# main.net
KiCad netlist of a schematic drawn in EAGLE
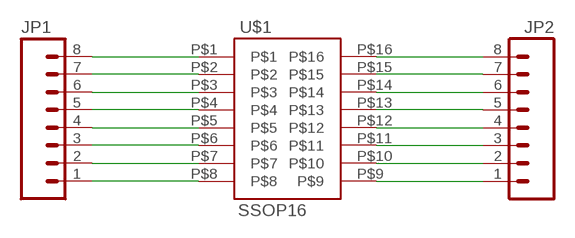
[diagram p0: schematic, sheet 1]

(export (version "E")
  (design (tool "Eeschema 10.0.6"))
  (components
    (comp (ref "JP1")
      (value "M08LONGPADS")
      (footprint "eagle-import:1X08_LONGPADS")
      (libsource (lib "eagle-import") (part "M08LONGPADS"))
    )
    (comp (ref "JP2")
      (value "M08LONGPADS")
      (footprint "eagle-import:1X08_LONGPADS")
      (libsource (lib "eagle-import") (part "M08LONGPADS"))
    )
    (comp (ref "U$1")
      (value "SSOP16")
      (footprint "eagle-import:SSOP16")
      (libsource (lib "eagle-import") (part "SSOP16"))
    )
  )
  (nets
    (net (code "1") (name "Net-(JP1-Pad1)") (class "Default")
      (node (ref "JP1") (pin "1") (pinfunction "1_1") (pintype "passive"))
      (node (ref "U$1") (pin "P$8") (pinfunction "P$8_P$8") (pintype "bidirectional"))
    )
    (net (code "2") (name "Net-(JP1-Pad2)") (class "Default")
      (node (ref "JP1") (pin "2") (pinfunction "2_2") (pintype "passive"))
      (node (ref "U$1") (pin "P$7") (pinfunction "P$7_P$7") (pintype "bidirectional"))
    )
    (net (code "3") (name "Net-(JP1-Pad3)") (class "Default")
      (node (ref "JP1") (pin "3") (pinfunction "3_3") (pintype "passive"))
      (node (ref "U$1") (pin "P$6") (pinfunction "P$6_P$6") (pintype "bidirectional"))
    )
    (net (code "4") (name "Net-(JP1-Pad4)") (class "Default")
      (node (ref "JP1") (pin "4") (pinfunction "4_4") (pintype "passive"))
      (node (ref "U$1") (pin "P$5") (pinfunction "P$5_P$5") (pintype "bidirectional"))
    )
    (net (code "5") (name "Net-(JP1-Pad5)") (class "Default")
      (node (ref "JP1") (pin "5") (pinfunction "5_5") (pintype "passive"))
      (node (ref "U$1") (pin "P$4") (pinfunction "P$4_P$4") (pintype "bidirectional"))
    )
    (net (code "6") (name "Net-(JP1-Pad6)") (class "Default")
      (node (ref "JP1") (pin "6") (pinfunction "6_6") (pintype "passive"))
      (node (ref "U$1") (pin "P$3") (pinfunction "P$3_P$3") (pintype "bidirectional"))
    )
    (net (code "7") (name "Net-(JP1-Pad7)") (class "Default")
      (node (ref "JP1") (pin "7") (pinfunction "7_7") (pintype "passive"))
      (node (ref "U$1") (pin "P$2") (pinfunction "P$2_P$2") (pintype "bidirectional"))
    )
    (net (code "8") (name "Net-(JP1-Pad8)") (class "Default")
      (node (ref "JP1") (pin "8") (pinfunction "8_8") (pintype "passive"))
      (node (ref "U$1") (pin "P$1") (pinfunction "P$1_P$1") (pintype "bidirectional"))
    )
    (net (code "9") (name "Net-(JP2-Pad1)") (class "Default")
      (node (ref "JP2") (pin "1") (pinfunction "1_1") (pintype "passive"))
      (node (ref "U$1") (pin "P$9") (pinfunction "P$9_P$9") (pintype "bidirectional"))
    )
    (net (code "10") (name "Net-(JP2-Pad2)") (class "Default")
      (node (ref "JP2") (pin "2") (pinfunction "2_2") (pintype "passive"))
      (node (ref "U$1") (pin "P$10") (pinfunction "P$10_P$10") (pintype "bidirectional"))
    )
    (net (code "11") (name "Net-(JP2-Pad3)") (class "Default")
      (node (ref "JP2") (pin "3") (pinfunction "3_3") (pintype "passive"))
      (node (ref "U$1") (pin "P$11") (pinfunction "P$11_P$11") (pintype "bidirectional"))
    )
    (net (code "12") (name "Net-(JP2-Pad4)") (class "Default")
      (node (ref "JP2") (pin "4") (pinfunction "4_4") (pintype "passive"))
      (node (ref "U$1") (pin "P$12") (pinfunction "P$12_P$12") (pintype "bidirectional"))
    )
    (net (code "13") (name "Net-(JP2-Pad5)") (class "Default")
      (node (ref "JP2") (pin "5") (pinfunction "5_5") (pintype "passive"))
      (node (ref "U$1") (pin "P$13") (pinfunction "P$13_P$13") (pintype "bidirectional"))
    )
    (net (code "14") (name "Net-(JP2-Pad6)") (class "Default")
      (node (ref "JP2") (pin "6") (pinfunction "6_6") (pintype "passive"))
      (node (ref "U$1") (pin "P$14") (pinfunction "P$14_P$14") (pintype "bidirectional"))
    )
    (net (code "15") (name "Net-(JP2-Pad7)") (class "Default")
      (node (ref "JP2") (pin "7") (pinfunction "7_7") (pintype "passive"))
      (node (ref "U$1") (pin "P$15") (pinfunction "P$15_P$15") (pintype "bidirectional"))
    )
    (net (code "16") (name "Net-(JP2-Pad8)") (class "Default")
      (node (ref "JP2") (pin "8") (pinfunction "8_8") (pintype "passive"))
      (node (ref "U$1") (pin "P$16") (pinfunction "P$16_P$16") (pintype "bidirectional"))
    )
  )
)
